# POWER_SUPPLY.net
KiCad netlist of a schematic drawn in Altium Designer
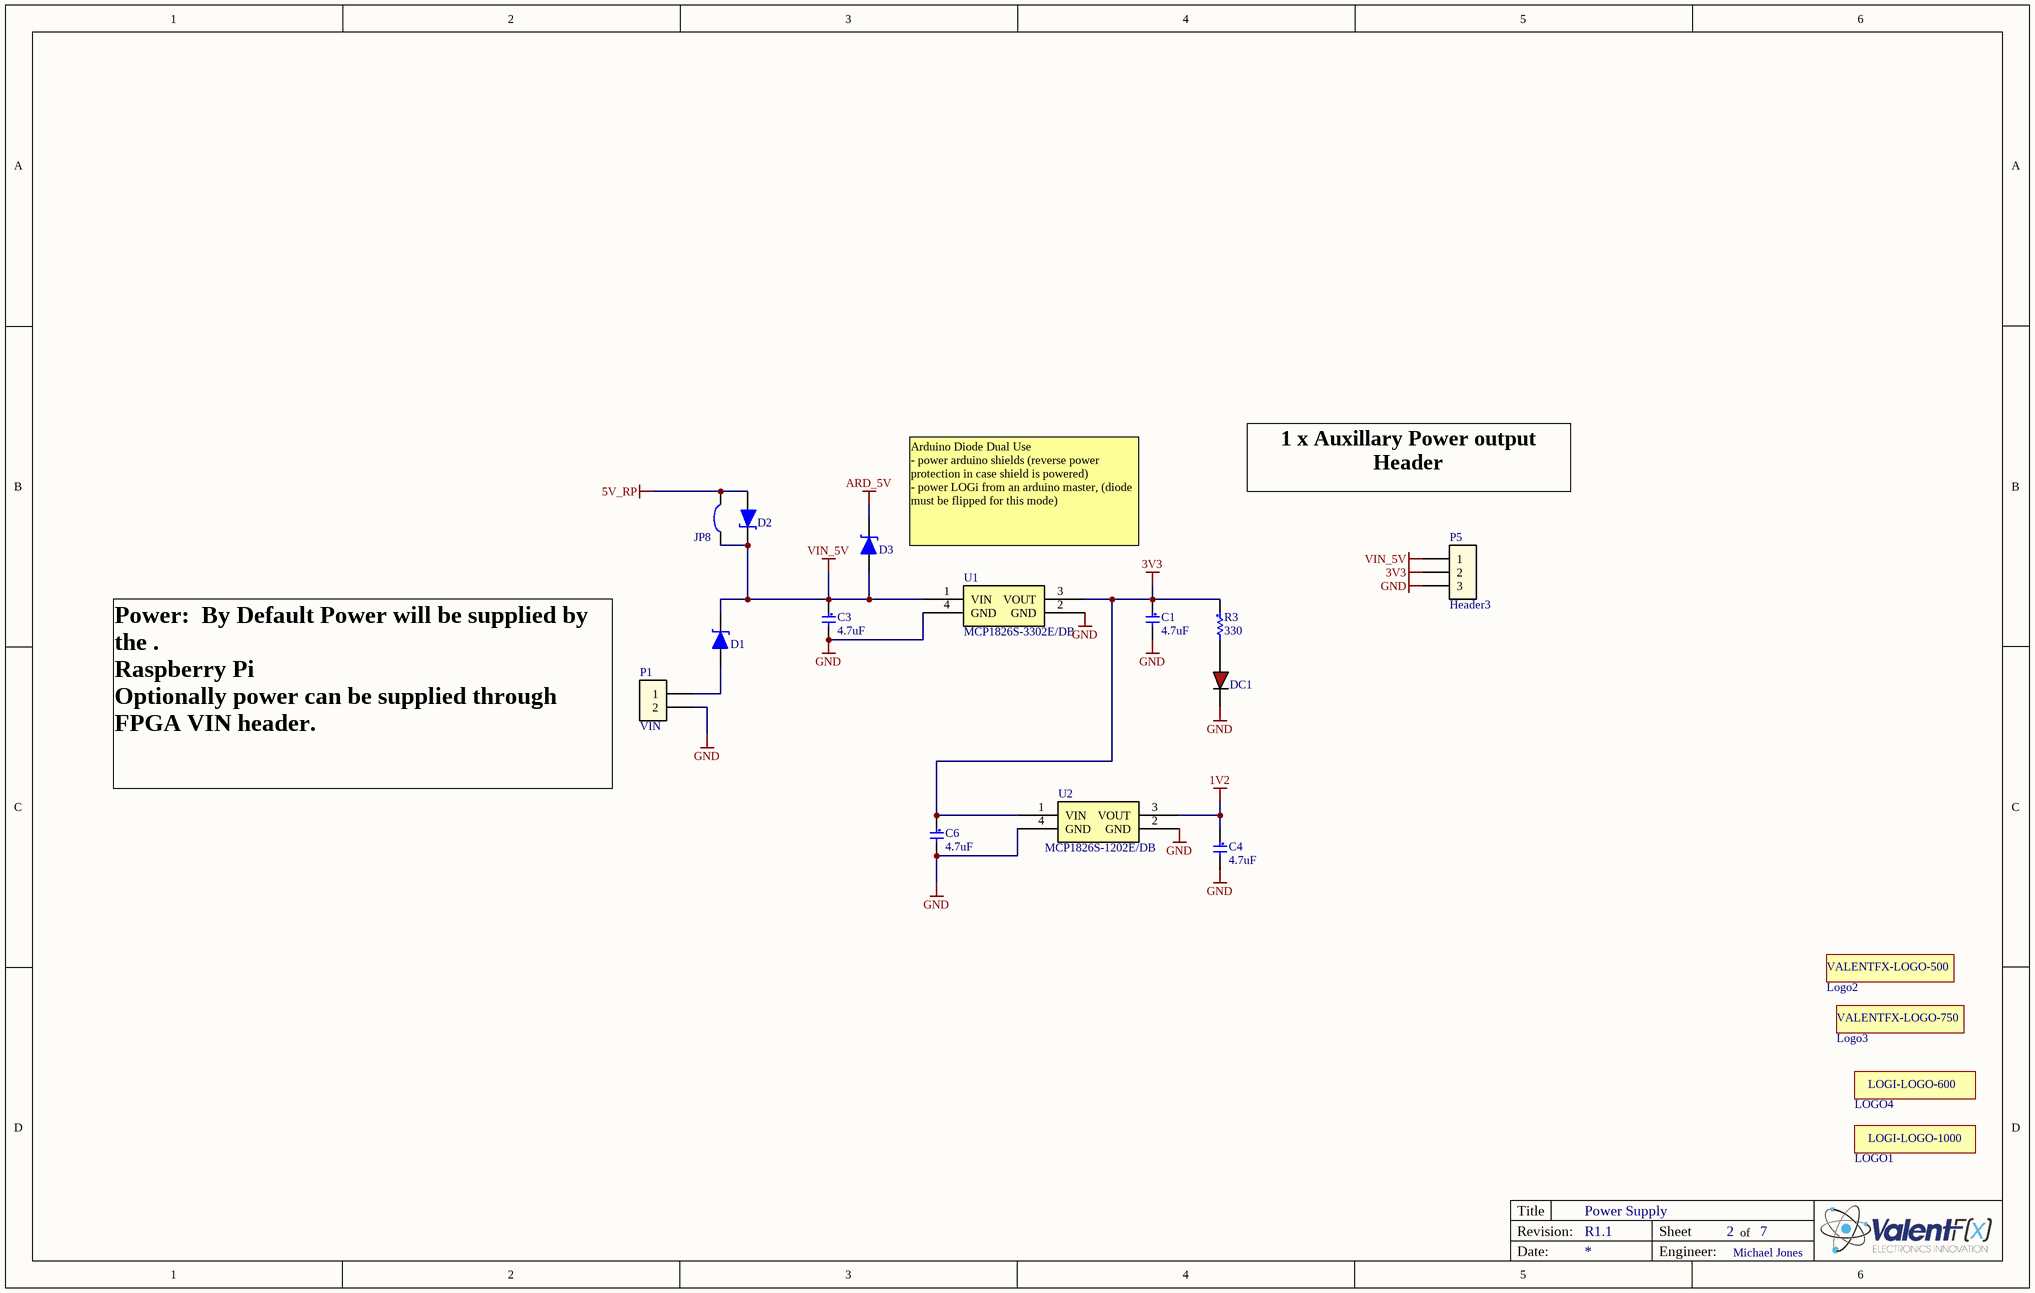
[diagram p0: POWER_SUPPLY.SchDoc]

(export (version "E")
  (design (tool "Eeschema 10.0.6"))
  (components
    (comp (ref "C1")
      (value "4.7uF")
      (footprint "C0603 - Marked")
      (description "4.7uF 6.3volts X5R 10% (MLCC) - SMD/SMT 0603")
      (fields
        (field (name "MANUFACTURER") "Murata Electronics North America")
        (field (name "MANUFACTURER PART NUMBER") "GRM188R60J475KE19D")
      )
      (libsource (lib "mCapacitors") (part "C0603 - GRM188R60J475KE19D"))
    )
    (comp (ref "C3")
      (value "4.7uF")
      (footprint "C0603 - Marked")
      (description "4.7uF 6.3volts X5R 10% (MLCC) - SMD/SMT 0603")
      (fields
        (field (name "MANUFACTURER") "Murata Electronics North America")
        (field (name "MANUFACTURER PART NUMBER") "GRM188R60J475KE19D")
      )
      (libsource (lib "mCapacitors") (part "C0603 - GRM188R60J475KE19D"))
    )
    (comp (ref "C4")
      (value "4.7uF")
      (footprint "C0603 - Marked")
      (description "4.7uF 6.3volts X5R 10% (MLCC) - SMD/SMT 0603")
      (fields
        (field (name "MANUFACTURER") "Murata Electronics North America")
        (field (name "MANUFACTURER PART NUMBER") "GRM188R60J475KE19D")
      )
      (libsource (lib "mCapacitors") (part "C0603 - GRM188R60J475KE19D"))
    )
    (comp (ref "C6")
      (value "4.7uF")
      (footprint "C0603 - Marked")
      (description "4.7uF 6.3volts X5R 10% (MLCC) - SMD/SMT 0603")
      (fields
        (field (name "MANUFACTURER") "Murata Electronics North America")
        (field (name "MANUFACTURER PART NUMBER") "GRM188R60J475KE19D")
      )
      (libsource (lib "mCapacitors") (part "C0603 - GRM188R60J475KE19D"))
    )
    (comp (ref "D1")
      (value "RB161M-20TR")
      (footprint "mdiode:SOD-123")
      (description "DIODE SCHOTTKY 25V 1A SOD123")
      (fields
        (field (name "MANUFACTURER") "Diodes Inc")
        (field (name "MANUFACTURER PART NUMBER") "Rohm Semiconductor")
        (field (name "SOURCE") "Digikey")
      )
      (libsource (lib "mDiode") (part "RB161M-20TR"))
    )
    (comp (ref "D2")
      (value "RB161M-20TR")
      (footprint "mdiode:SOD-123")
      (description "DIODE SCHOTTKY 25V 1A SOD123")
      (fields
        (field (name "MANUFACTURER") "Diodes Inc")
        (field (name "MANUFACTURER PART NUMBER") "Rohm Semiconductor")
        (field (name "SOURCE") "Digikey")
      )
      (libsource (lib "mDiode") (part "RB161M-20TR"))
    )
    (comp (ref "D3")
      (value "RB161M-20TR")
      (footprint "mdiode:SOD-123")
      (description "DIODE SCHOTTKY 25V 1A SOD123")
      (fields
        (field (name "MANUFACTURER") "Diodes Inc")
        (field (name "MANUFACTURER PART NUMBER") "Rohm Semiconductor")
        (field (name "SOURCE") "Digikey")
      )
      (libsource (lib "mDiode") (part "RB161M-20TR"))
    )
    (comp (ref "DC1")
      (value "598-8010-107F")
      (footprint "LED_0603 - RED")
      (description "LED ALINGAP RED CLEAR 0603 SMD")
      (fields (field (name "MANUFACTURER") "Dialight"))
      (libsource (lib "mDiode") (part "LED0603 - 598-8010-107F"))
    )
    (comp (ref "JP8")
      (value "Solder Jumper")
      (footprint "SOLDER_JUMPER")
      (description "Solder/Configuration Jumper")
      (fields (field (name "MANUFACTURER") "n/a"))
      (libsource (lib "mConnector") (part "Solder Jumper"))
    )
    (comp (ref "LOGO1")
      (value "LOGI-1000")
      (footprint "LOGI-1000-SILK")
      (libsource (lib "mLogos") (part "LOGI-1000"))
    )
    (comp (ref "Logo2")
      (value "Valent Logo 500")
      (footprint "VALENTFX_500-SolderMask")
      (libsource (lib "mLogos") (part "Valent Logo 500"))
    )
    (comp (ref "Logo3")
      (value "Valent Logo 750")
      (footprint "VALENTFX_750-SolderMask")
      (libsource (lib "mLogos") (part "Valent Logo 750"))
    )
    (comp (ref "LOGO4")
      (value "LOGI-600")
      (footprint "LOGI-600-SILK")
      (libsource (lib "mLogos") (part "LOGI-600"))
    )
    (comp (ref "P1")
      (value "VIN")
      (footprint "HEADER_2_40_100 THRU SIP")
      (description "Header 2 pin")
      (libsource (lib "mConnector") (part "Header2"))
    )
    (comp (ref "P5")
      (value "Header3")
      (footprint "HEADER_3_40_100 THRU SIP")
      (description "Header  pin")
      (libsource (lib "mConnector") (part "Header3"))
    )
    (comp (ref "R3")
      (value "330")
      (footprint "R0603")
      (description "Thick Film Resistors - SMD 0603 330ohms 5% Tol")
      (fields
        (field (name "MANUFACTURER") "Panasonic")
        (field (name "MANUFACTURER PART NUMBER") "ERJ-3GEYJ331V")
      )
      (libsource (lib "mResistors") (part "R0603 - ERJ-3GEYJ331V"))
    )
    (comp (ref "U1")
      (value "MCP1826S-3302E/DB")
      (footprint "SOT223")
      (description "LDO REG 1A 3.3V SOT223-3")
      (fields (field (name "MANUFACTURER") "Microchip Technology"))
      (libsource (lib "mIC") (part "REG - MCP1826S-3302E/DB"))
    )
    (comp (ref "U2")
      (value "MCP1826S-1202E/DB")
      (footprint "SOT223")
      (description "IC LDO REG 1A 1.2V SOT223-3")
      (fields (field (name "MANUFACTURER") "Microchip Technology"))
      (libsource (lib "eIC") (part "MCP1826S-1202E/DB"))
    )
  )
  (nets
    (net (code "1") (name "1V2") (class "Default")
      (node (ref "C4") (pin "1") (pinfunction "1_1") (pintype "passive"))
      (node (ref "U2") (pin "3") (pinfunction "VOUT_3") (pintype "passive"))
    )
    (net (code "2") (name "3V3") (class "Default")
      (node (ref "C1") (pin "1") (pinfunction "1_1") (pintype "passive"))
      (node (ref "C6") (pin "1") (pinfunction "1_1") (pintype "passive"))
      (node (ref "P5") (pin "2") (pinfunction "2_2") (pintype "passive"))
      (node (ref "R3") (pin "1") (pinfunction "1_1") (pintype "passive"))
      (node (ref "U1") (pin "3") (pinfunction "VOUT_3") (pintype "passive"))
      (node (ref "U2") (pin "1") (pinfunction "VIN_1") (pintype "passive"))
    )
    (net (code "3") (name "5V_RP") (class "Default")
      (node (ref "D2") (pin "2") (pinfunction "A_2") (pintype "passive"))
      (node (ref "JP8") (pin "1") (pinfunction "1_1") (pintype "passive"))
    )
    (net (code "4") (name "ARD_5V") (class "Default")
      (node (ref "D3") (pin "1") (pinfunction "C_1") (pintype "passive"))
    )
    (net (code "5") (name "GND") (class "Default")
      (node (ref "C1") (pin "2") (pinfunction "2_2") (pintype "passive"))
      (node (ref "C3") (pin "2") (pinfunction "2_2") (pintype "passive"))
      (node (ref "C4") (pin "2") (pinfunction "2_2") (pintype "passive"))
      (node (ref "C6") (pin "2") (pinfunction "2_2") (pintype "passive"))
      (node (ref "DC1") (pin "C") (pinfunction "C_C") (pintype "passive"))
      (node (ref "P1") (pin "2") (pinfunction "2_2") (pintype "passive"))
      (node (ref "P5") (pin "3") (pinfunction "3_3") (pintype "passive"))
      (node (ref "U1") (pin "2") (pinfunction "GND_2") (pintype "passive"))
      (node (ref "U1") (pin "4") (pinfunction "GND_4") (pintype "passive"))
      (node (ref "U2") (pin "2") (pinfunction "GND_2") (pintype "passive"))
      (node (ref "U2") (pin "4") (pinfunction "GND_4") (pintype "passive"))
    )
    (net (code "6") (name "Net-(D1-A)") (class "Default")
      (node (ref "D1") (pin "2") (pinfunction "A_2") (pintype "passive"))
      (node (ref "P1") (pin "1") (pinfunction "1_1") (pintype "passive"))
    )
    (net (code "7") (name "Net-(DC1-PadA)") (class "Default")
      (node (ref "DC1") (pin "A") (pinfunction "A_A") (pintype "passive"))
      (node (ref "R3") (pin "2") (pinfunction "2_2") (pintype "passive"))
    )
    (net (code "8") (name "VIN_5V") (class "Default")
      (node (ref "C3") (pin "1") (pinfunction "1_1") (pintype "passive"))
      (node (ref "D1") (pin "1") (pinfunction "C_1") (pintype "passive"))
      (node (ref "D2") (pin "1") (pinfunction "C_1") (pintype "passive"))
      (node (ref "D3") (pin "2") (pinfunction "A_2") (pintype "passive"))
      (node (ref "JP8") (pin "2") (pinfunction "2_2") (pintype "passive"))
      (node (ref "P5") (pin "1") (pinfunction "1_1") (pintype "passive"))
      (node (ref "U1") (pin "1") (pinfunction "VIN_1") (pintype "passive"))
    )
  )
)
